# Battery_circuit.net
KiCad netlist of a schematic drawn in Altium Designer
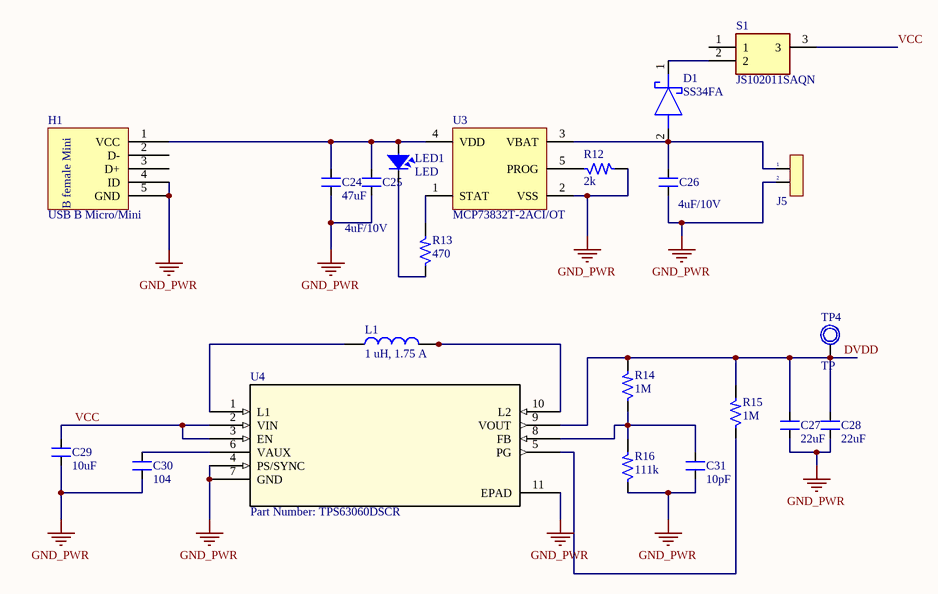
[diagram p0: Battery circuit.SchDoc]

(export (version "E")
  (design (tool "Eeschema 10.0.6"))
  (components
    (comp (ref "C24")
      (value "47uF")
      (footprint "SM-0805")
      (description "Cap SMD")
      (libsource (lib "VioletofSun") (part "CM"))
    )
    (comp (ref "C25")
      (value "4uF/10V")
      (footprint "SM-0805")
      (description "Cap SMD")
      (libsource (lib "VioletofSun") (part "CM"))
    )
    (comp (ref "C26")
      (value "4uF/10V")
      (footprint "SM-0805")
      (description "Cap SMD")
      (libsource (lib "VioletofSun") (part "CM"))
    )
    (comp (ref "C27")
      (value "22uF")
      (footprint "SM-0805")
      (description "Cap SMD")
      (libsource (lib "VioletofSun") (part "CM"))
    )
    (comp (ref "C28")
      (value "22uF")
      (footprint "SM-0805")
      (description "Cap SMD")
      (libsource (lib "VioletofSun") (part "CM"))
    )
    (comp (ref "C29")
      (value "10uF")
      (footprint "SM-0805")
      (description "Cap SMD")
      (libsource (lib "VioletofSun") (part "CM"))
    )
    (comp (ref "C30")
      (value "104")
      (footprint "SM-0805")
      (description "Cap SMD")
      (libsource (lib "VioletofSun") (part "CM"))
    )
    (comp (ref "C31")
      (value "10pF")
      (footprint "SM-0805")
      (description "Cap SMD")
      (libsource (lib "VioletofSun") (part "CM"))
    )
    (comp (ref "D1")
      (value "SS34FA")
      (footprint "SamacSys:SODFL3618X143N")
      (description "Schottky Diode")
      (fields (field (name "MOUSER PART NUMBER") "512-SS34FA"))
      (libsource (lib "*") (part "SS34FA"))
    )
    (comp (ref "H1")
      (value "USB B Micro/Mini")
      (footprint "USB-B-MICRO-female Tai02")
      (description "USB B Female Micro/Mini SMD")
      (libsource (lib "mylib") (part "USB B Female Micro/Mini SMD"))
    )
    (comp (ref "J5")
      (value "Jumper 2")
      (footprint "J2_Jst SH_1mm")
      (libsource (lib "VioletofSun") (part "JP 2"))
    )
    (comp (ref "L1")
      (value "1 uH, 1.75 A")
      (footprint "WE-TPC_2811")
      (description "SMT Shielded Tiny Power Inductor WE-TPC, size 2811, 1 uH, 1.75 A")
      (fields (field (name "PART NUMBER") "744028001") (field (name "PUBLISHER") "Wurth Elektronik"))
      (libsource (lib "ALTIUM-WE-TPC-rev18a") (part "744028001"))
    )
    (comp (ref "LED1")
      (value "LED")
      (footprint "SM-0805")
      (description "LED Single colour Green and Red")
      (libsource (lib "VioletofSun") (part "LED"))
    )
    (comp (ref "R12")
      (value "2k")
      (footprint "SM-0805")
      (description "Resistor 1/4W")
      (libsource (lib "VioletofSun") (part "R"))
    )
    (comp (ref "R13")
      (value "470")
      (footprint "SM-0805")
      (description "Resistor 1/4W")
      (libsource (lib "VioletofSun") (part "R"))
    )
    (comp (ref "R14")
      (value "1M")
      (footprint "SM-0805")
      (description "Resistor 1/4W")
      (libsource (lib "VioletofSun") (part "R"))
    )
    (comp (ref "R15")
      (value "1M")
      (footprint "SM-0805")
      (description "Resistor 1/4W")
      (libsource (lib "VioletofSun") (part "R"))
    )
    (comp (ref "R16")
      (value "111k")
      (footprint "SM-0805")
      (description "Resistor 1/4W")
      (libsource (lib "VioletofSun") (part "R"))
    )
    (comp (ref "S1")
      (value "JS102011SAQN")
      (footprint "SamacSys:JS102011SAQN")
      (description "Switch")
      (fields
        (field (name "MOUSER PART NUMBER") "611-JS102011SAQN")
        (field (name "RS PART NUMBER") "1543603")
      )
      (libsource (lib "*") (part "JS102011SAQN"))
    )
    (comp (ref "TP4")
      (value "TP")
      (footprint "VioletofSun:TP1")
      (description "Test Point")
      (libsource (lib "VioletofSun") (part "TP1"))
    )
    (comp (ref "U3")
      (value "MCP73832T-2ACI/OT")
      (footprint "SOT-23-OT5_N")
      (fields (field (name "PUBLISHER") "Altium Limited"))
      (libsource (lib "Microchip Power Mgt Battery Management") (part "MCP73832T-2ACI/OT"))
    )
    (comp (ref "U4")
      (value "Part Number: TPS63060DSCR")
      (footprint "DSC10_1P70X2P15")
      (description "No Description Available")
      (fields
        (field (name "MANUFACTURER_PART_NUMBER") "TPS63060DSCR")
        (field (name "MANUFACTURER") "Texas Instruments")
        (field (name "COPYRIGHT") "Copyright (C) 2018 Accelerated Designs. All rights reserved")
      )
      (libsource (lib "2019-06-25_17-28-37") (part "TPS63060DSCR"))
    )
  )
  (nets
    (net (code "1") (name "/DVDD") (class "Default")
      (node (ref "C27") (pin "2") (pinfunction "2_2") (pintype "passive"))
      (node (ref "C28") (pin "2") (pinfunction "2_2") (pintype "passive"))
      (node (ref "R14") (pin "2") (pinfunction "2_2") (pintype "passive"))
      (node (ref "R15") (pin "2") (pinfunction "2_2") (pintype "passive"))
      (node (ref "TP4") (pin "1") (pinfunction "1_1") (pintype "passive"))
      (node (ref "U4") (pin "9") (pinfunction "VOUT_9") (pintype "output"))
    )
    (net (code "2") (name "/VCC") (class "Default")
      (node (ref "C29") (pin "2") (pinfunction "2_2") (pintype "passive"))
      (node (ref "S1") (pin "3") (pinfunction "3_3") (pintype "passive"))
      (node (ref "U4") (pin "2") (pinfunction "VIN_2") (pintype "input"))
      (node (ref "U4") (pin "3") (pinfunction "EN_3") (pintype "input"))
    )
    (net (code "3") (name "GND_PWR") (class "Default")
      (node (ref "C24") (pin "1") (pinfunction "1_1") (pintype "passive"))
      (node (ref "C25") (pin "1") (pinfunction "1_1") (pintype "passive"))
      (node (ref "C26") (pin "1") (pinfunction "1_1") (pintype "passive"))
      (node (ref "C27") (pin "1") (pinfunction "1_1") (pintype "passive"))
      (node (ref "C28") (pin "1") (pinfunction "1_1") (pintype "passive"))
      (node (ref "C29") (pin "1") (pinfunction "1_1") (pintype "passive"))
      (node (ref "C30") (pin "1") (pinfunction "1_1") (pintype "passive"))
      (node (ref "C31") (pin "1") (pinfunction "1_1") (pintype "passive"))
      (node (ref "H1") (pin "4") (pinfunction "ID_4") (pintype "passive"))
      (node (ref "H1") (pin "5") (pinfunction "GND_5") (pintype "passive"))
      (node (ref "J5") (pin "2") (pinfunction "2_2") (pintype "passive"))
      (node (ref "R12") (pin "2") (pinfunction "2_2") (pintype "passive"))
      (node (ref "R16") (pin "1") (pinfunction "1_1") (pintype "passive"))
      (node (ref "U3") (pin "2") (pinfunction "VSS_2") (pintype "power_in"))
      (node (ref "U4") (pin "11") (pinfunction "EPAD_11") (pintype "passive"))
      (node (ref "U4") (pin "4") (pinfunction "PS/SYNC_4") (pintype "input"))
      (node (ref "U4") (pin "7") (pinfunction "GND_7") (pintype "power_in"))
    )
    (net (code "4") (name "Net-(D1-A)") (class "Default")
      (node (ref "C26") (pin "2") (pinfunction "2_2") (pintype "passive"))
      (node (ref "D1") (pin "2") (pinfunction "A_2") (pintype "passive"))
      (node (ref "J5") (pin "1") (pinfunction "1_1") (pintype "passive"))
      (node (ref "U3") (pin "3") (pinfunction "VBAT_3") (pintype "power_in"))
    )
    (net (code "5") (name "Net-(D1-K)") (class "Default")
      (node (ref "D1") (pin "1") (pinfunction "K_1") (pintype "passive"))
      (node (ref "S1") (pin "2") (pinfunction "2_2") (pintype "passive"))
    )
    (net (code "6") (name "Net-(H1-VCC)") (class "Default")
      (node (ref "C24") (pin "2") (pinfunction "2_2") (pintype "passive"))
      (node (ref "C25") (pin "2") (pinfunction "2_2") (pintype "passive"))
      (node (ref "H1") (pin "1") (pinfunction "VCC_1") (pintype "passive"))
      (node (ref "LED1") (pin "1") (pinfunction "1_1") (pintype "passive"))
      (node (ref "U3") (pin "4") (pinfunction "VDD_4") (pintype "power_in"))
    )
    (net (code "7") (name "Net-(LED1-Pad2)") (class "Default")
      (node (ref "LED1") (pin "2") (pinfunction "2_2") (pintype "passive"))
      (node (ref "R13") (pin "1") (pinfunction "1_1") (pintype "passive"))
    )
    (net (code "8") (name "Net-(U3-PROG)") (class "Default")
      (node (ref "R12") (pin "1") (pinfunction "1_1") (pintype "passive"))
      (node (ref "U3") (pin "5") (pinfunction "PROG_5") (pintype "passive"))
    )
    (net (code "9") (name "Net-(U3-STAT)") (class "Default")
      (node (ref "R13") (pin "2") (pinfunction "2_2") (pintype "passive"))
      (node (ref "U3") (pin "1") (pinfunction "STAT_1") (pintype "open_collector"))
    )
    (net (code "10") (name "Net-(U4-FB)") (class "Default")
      (node (ref "C31") (pin "2") (pinfunction "2_2") (pintype "passive"))
      (node (ref "R14") (pin "1") (pinfunction "1_1") (pintype "passive"))
      (node (ref "R16") (pin "2") (pinfunction "2_2") (pintype "passive"))
      (node (ref "U4") (pin "8") (pinfunction "FB_8") (pintype "input"))
    )
    (net (code "11") (name "Net-(U4-L1)") (class "Default")
      (node (ref "L1") (pin "1") (pinfunction "1_1") (pintype "passive"))
      (node (ref "U4") (pin "1") (pinfunction "L1_1") (pintype "input"))
    )
    (net (code "12") (name "Net-(U4-L2)") (class "Default")
      (node (ref "L1") (pin "2") (pinfunction "2_2") (pintype "passive"))
      (node (ref "U4") (pin "10") (pinfunction "L2_10") (pintype "input"))
    )
    (net (code "13") (name "Net-(U4-PG)") (class "Default")
      (node (ref "R15") (pin "1") (pinfunction "1_1") (pintype "passive"))
      (node (ref "U4") (pin "5") (pinfunction "PG_5") (pintype "output"))
    )
    (net (code "14") (name "Net-(U4-VAUX)") (class "Default")
      (node (ref "C30") (pin "2") (pinfunction "2_2") (pintype "passive"))
      (node (ref "U4") (pin "6") (pinfunction "VAUX_6") (pintype "passive"))
    )
    (net (code "15") (name "unconnected-(H1-D+-Pad3)") (class "Default")
      (node (ref "H1") (pin "3") (pinfunction "D+_3") (pintype "passive"))
    )
    (net (code "16") (name "unconnected-(H1-D--Pad2)") (class "Default")
      (node (ref "H1") (pin "2") (pinfunction "D-_2") (pintype "passive"))
    )
    (net (code "17") (name "unconnected-(S1-Pad1)") (class "Default")
      (node (ref "S1") (pin "1") (pinfunction "1_1") (pintype "passive"))
    )
  )
)
